# -46342_21-004_3_2.net
KiCad netlist of a schematic drawn in Altium Designer
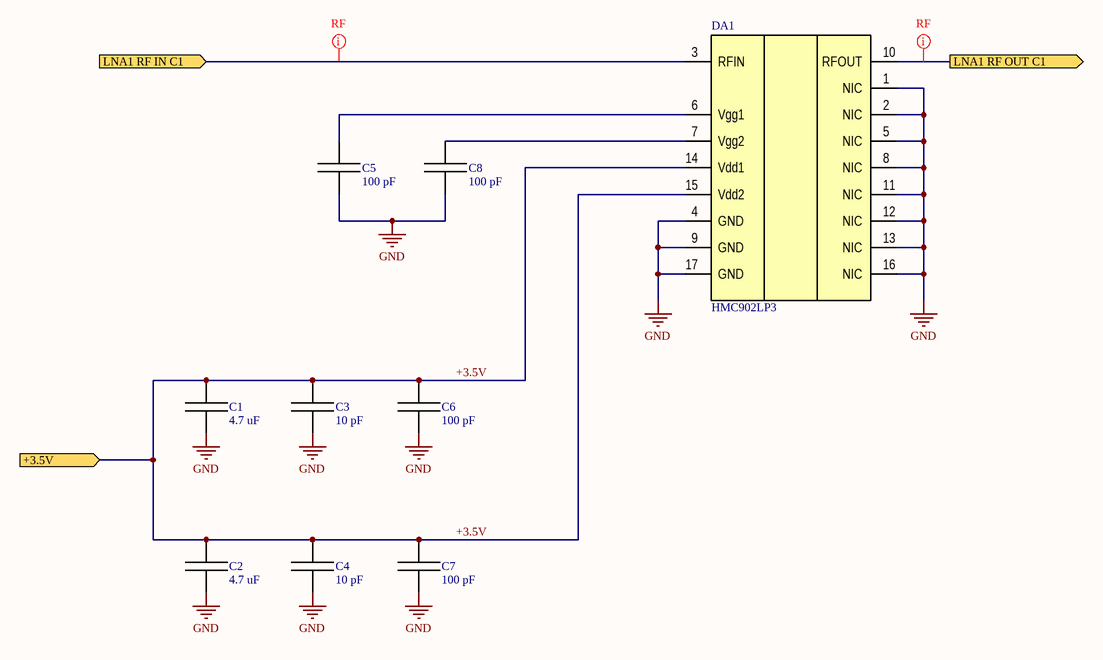
[diagram p0: МПСУ-46342.21-004 Э3 Лист2.SchDoc]

(export (version "E")
  (design (tool "Eeschema 10.0.6"))
  (components
    (comp (ref "C1")
      (value "4.7 uF")
      (footprint "CAPC160X80X90L30N")
      (description "Capacitor, generic")
      (fields (field (name "TOLERANCE") "5 %"))
      (libsource (lib "StudentsLibrary") (part "Capacitor"))
    )
    (comp (ref "C2")
      (value "4.7 uF")
      (footprint "CAPC160X80X90L30N")
      (description "Capacitor, generic")
      (fields (field (name "TOLERANCE") "5 %"))
      (libsource (lib "StudentsLibrary") (part "Capacitor"))
    )
    (comp (ref "C3")
      (value "10 pF")
      (footprint "CAPC100X50X55L20N")
      (description "Capacitor, generic")
      (fields (field (name "TOLERANCE") "5 %"))
      (libsource (lib "StudentsLibrary") (part "Capacitor"))
    )
    (comp (ref "C4")
      (value "10 pF")
      (footprint "CAPC100X50X55L20N")
      (description "Capacitor, generic")
      (fields (field (name "TOLERANCE") "5 %"))
      (libsource (lib "StudentsLibrary") (part "Capacitor"))
    )
    (comp (ref "C5")
      (value "100 pF")
      (footprint "CAPC100X50X55L20N")
      (description "Capacitor, generic")
      (fields (field (name "TOLERANCE") "5 %"))
      (libsource (lib "StudentsLibrary") (part "Capacitor"))
    )
    (comp (ref "C6")
      (value "100 pF")
      (footprint "CAPC100X50X55L20N")
      (description "Capacitor, generic")
      (fields (field (name "TOLERANCE") "5 %"))
      (libsource (lib "StudentsLibrary") (part "Capacitor"))
    )
    (comp (ref "C7")
      (value "100 pF")
      (footprint "CAPC100X50X55L20N")
      (description "Capacitor, generic")
      (fields (field (name "TOLERANCE") "5 %"))
      (libsource (lib "StudentsLibrary") (part "Capacitor"))
    )
    (comp (ref "C8")
      (value "100 pF")
      (footprint "CAPC100X50X55L20N")
      (description "Capacitor, generic")
      (fields (field (name "TOLERANCE") "5 %"))
      (libsource (lib "StudentsLibrary") (part "Capacitor"))
    )
    (comp (ref "DA1")
      (value "HMC902LP3")
      (footprint "QFN17P50_300X300X90L40X25T170N")
      (description "GaAs, pHEMT, MMIC, Low Noise Amplifier, 5 GHz to 11 GHz")
      (fields (field (name "MANUFACTURER") "Analog Devices"))
      (libsource (lib "receiver") (part "HMC902LP3"))
    )
  )
  (nets
    (net (code "1") (name "/+3.5V") (class "Default")
      (node (ref "C1") (pin "2") (pinfunction "2_2") (pintype "passive"))
      (node (ref "C2") (pin "2") (pinfunction "2_2") (pintype "passive"))
      (node (ref "C3") (pin "2") (pinfunction "2_2") (pintype "passive"))
      (node (ref "C4") (pin "2") (pinfunction "2_2") (pintype "passive"))
      (node (ref "C6") (pin "2") (pinfunction "2_2") (pintype "passive"))
      (node (ref "C7") (pin "2") (pinfunction "2_2") (pintype "passive"))
      (node (ref "DA1") (pin "14") (pinfunction "Vdd1_14") (pintype "passive"))
      (node (ref "DA1") (pin "15") (pinfunction "Vdd2_15") (pintype "passive"))
    )
    (net (code "2") (name "/LNA1 RF IN C1") (class "Default")
      (node (ref "DA1") (pin "3") (pinfunction "RFIN_3") (pintype "passive"))
    )
    (net (code "3") (name "/LNA1 RF OUT C1") (class "Default")
      (node (ref "DA1") (pin "10") (pinfunction "RFOUT_10") (pintype "passive"))
    )
    (net (code "4") (name "GND") (class "Default")
      (node (ref "C1") (pin "1") (pinfunction "1_1") (pintype "passive"))
      (node (ref "C2") (pin "1") (pinfunction "1_1") (pintype "passive"))
      (node (ref "C3") (pin "1") (pinfunction "1_1") (pintype "passive"))
      (node (ref "C4") (pin "1") (pinfunction "1_1") (pintype "passive"))
      (node (ref "C5") (pin "1") (pinfunction "1_1") (pintype "passive"))
      (node (ref "C6") (pin "1") (pinfunction "1_1") (pintype "passive"))
      (node (ref "C7") (pin "1") (pinfunction "1_1") (pintype "passive"))
      (node (ref "C8") (pin "1") (pinfunction "1_1") (pintype "passive"))
      (node (ref "DA1") (pin "1") (pinfunction "NIC_1") (pintype "passive"))
      (node (ref "DA1") (pin "11") (pinfunction "NIC_11") (pintype "passive"))
      (node (ref "DA1") (pin "12") (pinfunction "NIC_12") (pintype "passive"))
      (node (ref "DA1") (pin "13") (pinfunction "NIC_13") (pintype "passive"))
      (node (ref "DA1") (pin "16") (pinfunction "NIC_16") (pintype "passive"))
      (node (ref "DA1") (pin "17") (pinfunction "GND_17") (pintype "passive"))
      (node (ref "DA1") (pin "2") (pinfunction "NIC_2") (pintype "passive"))
      (node (ref "DA1") (pin "4") (pinfunction "GND_4") (pintype "passive"))
      (node (ref "DA1") (pin "5") (pinfunction "NIC_5") (pintype "passive"))
      (node (ref "DA1") (pin "8") (pinfunction "NIC_8") (pintype "passive"))
      (node (ref "DA1") (pin "9") (pinfunction "GND_9") (pintype "passive"))
    )
    (net (code "5") (name "Net-(DA1-Vgg1)") (class "Default")
      (node (ref "C5") (pin "2") (pinfunction "2_2") (pintype "passive"))
      (node (ref "DA1") (pin "6") (pinfunction "Vgg1_6") (pintype "passive"))
    )
    (net (code "6") (name "Net-(DA1-Vgg2)") (class "Default")
      (node (ref "C8") (pin "2") (pinfunction "2_2") (pintype "passive"))
      (node (ref "DA1") (pin "7") (pinfunction "Vgg2_7") (pintype "passive"))
    )
  )
)
